# buttons.net
KiCad netlist of a schematic drawn in Altium Designer
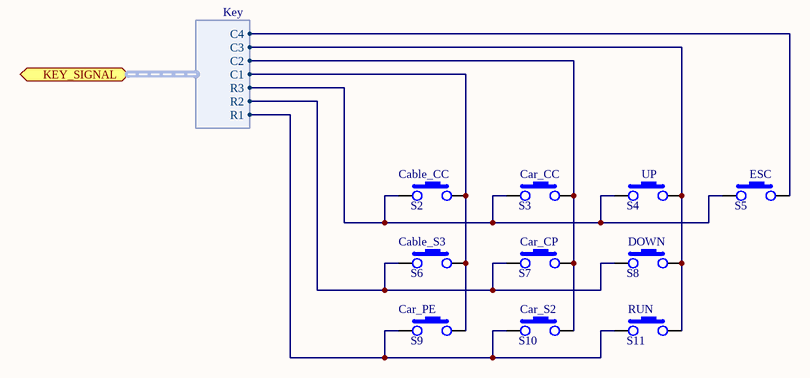
[diagram p0: buttons.SchDoc]

(export (version "E")
  (design (tool "Eeschema 10.0.6"))
  (components
    (comp (ref "S2")
      (value "SKHCBJA010")
      (footprint "UserPcbLib:SKHCBJA010")
      (description "Alps tact switch 12x12")
      (libsource (lib "UserSchlib") (part "SKHCBJA010"))
    )
    (comp (ref "S3")
      (value "SKHCBJA010")
      (footprint "UserPcbLib:SKHCBJA010")
      (description "Alps tact switch 12x12")
      (libsource (lib "UserSchlib") (part "SKHCBJA010"))
    )
    (comp (ref "S4")
      (value "SKHCBJA010")
      (footprint "UserPcbLib:SKHCBJA010")
      (description "Alps tact switch 12x12")
      (libsource (lib "UserSchlib") (part "SKHCBJA010"))
    )
    (comp (ref "S5")
      (value "SKHCBJA010")
      (footprint "UserPcbLib:SKHCBJA010")
      (description "Alps tact switch 12x12")
      (libsource (lib "UserSchlib") (part "SKHCBJA010"))
    )
    (comp (ref "S6")
      (value "SKHCBJA010")
      (footprint "UserPcbLib:SKHCBJA010")
      (description "Alps tact switch 12x12")
      (libsource (lib "UserSchlib") (part "SKHCBJA010"))
    )
    (comp (ref "S7")
      (value "SKHCBJA010")
      (footprint "UserPcbLib:SKHCBJA010")
      (description "Alps tact switch 12x12")
      (libsource (lib "UserSchlib") (part "SKHCBJA010"))
    )
    (comp (ref "S8")
      (value "SKHCBJA010")
      (footprint "UserPcbLib:SKHCBJA010")
      (description "Alps tact switch 12x12")
      (libsource (lib "UserSchlib") (part "SKHCBJA010"))
    )
    (comp (ref "S9")
      (value "SKHCBJA010")
      (footprint "UserPcbLib:SKHCBJA010")
      (description "Alps tact switch 12x12")
      (libsource (lib "UserSchlib") (part "SKHCBJA010"))
    )
    (comp (ref "S10")
      (value "SKHCBJA010")
      (footprint "UserPcbLib:SKHCBJA010")
      (description "Alps tact switch 12x12")
      (libsource (lib "UserSchlib") (part "SKHCBJA010"))
    )
    (comp (ref "S11")
      (value "SKHCBJA010")
      (footprint "UserPcbLib:SKHCBJA010")
      (description "Alps tact switch 12x12")
      (libsource (lib "UserSchlib") (part "SKHCBJA010"))
    )
  )
  (nets
    (net (code "2") (name "/C1") (class "Default")
      (node (ref "S2") (pin "3") (pinfunction "3_3") (pintype "passive"))
      (node (ref "S6") (pin "3") (pinfunction "3_3") (pintype "passive"))
      (node (ref "S9") (pin "3") (pinfunction "3_3") (pintype "passive"))
    )
    (net (code "3") (name "/C2") (class "Default")
      (node (ref "S10") (pin "3") (pinfunction "3_3") (pintype "passive"))
      (node (ref "S3") (pin "3") (pinfunction "3_3") (pintype "passive"))
      (node (ref "S7") (pin "3") (pinfunction "3_3") (pintype "passive"))
    )
    (net (code "4") (name "/C3") (class "Default")
      (node (ref "S11") (pin "3") (pinfunction "3_3") (pintype "passive"))
      (node (ref "S4") (pin "3") (pinfunction "3_3") (pintype "passive"))
      (node (ref "S8") (pin "3") (pinfunction "3_3") (pintype "passive"))
    )
    (net (code "5") (name "/C4") (class "Default")
      (node (ref "S5") (pin "3") (pinfunction "3_3") (pintype "passive"))
    )
    (net (code "6") (name "/R1") (class "Default")
      (node (ref "S10") (pin "1") (pinfunction "1_1") (pintype "passive"))
      (node (ref "S11") (pin "1") (pinfunction "1_1") (pintype "passive"))
      (node (ref "S9") (pin "1") (pinfunction "1_1") (pintype "passive"))
    )
    (net (code "7") (name "/R2") (class "Default")
      (node (ref "S6") (pin "1") (pinfunction "1_1") (pintype "passive"))
      (node (ref "S7") (pin "1") (pinfunction "1_1") (pintype "passive"))
      (node (ref "S8") (pin "1") (pinfunction "1_1") (pintype "passive"))
    )
    (net (code "8") (name "/R3") (class "Default")
      (node (ref "S2") (pin "1") (pinfunction "1_1") (pintype "passive"))
      (node (ref "S3") (pin "1") (pinfunction "1_1") (pintype "passive"))
      (node (ref "S4") (pin "1") (pinfunction "1_1") (pintype "passive"))
      (node (ref "S5") (pin "1") (pinfunction "1_1") (pintype "passive"))
    )
  )
)
